# Ciruit_Analyzer.net
KiCad netlist of a schematic drawn in Altium Designer
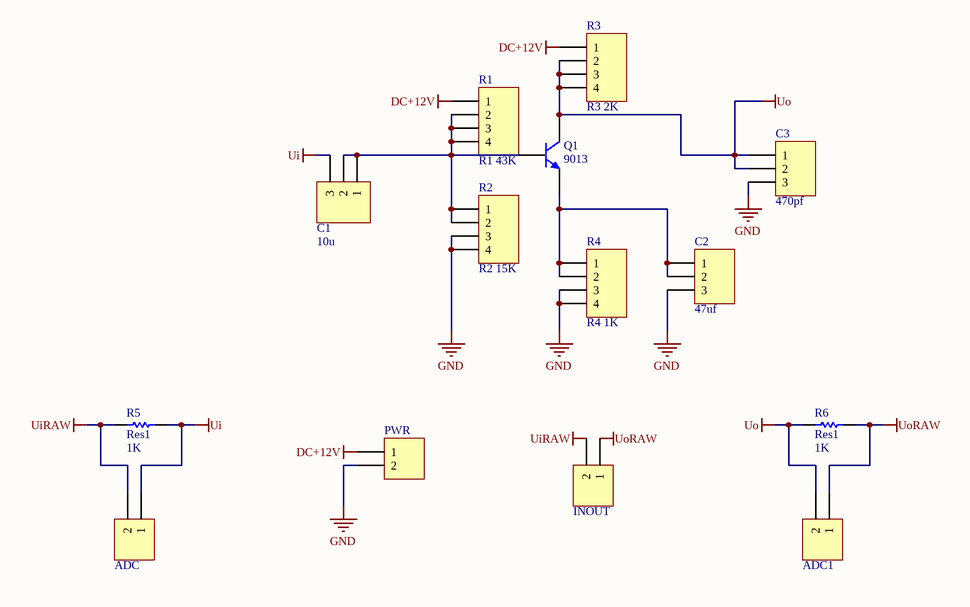
[diagram p0: Ciruit_Analyzer.SchDoc]

(export (version "E")
  (design (tool "Eeschema 10.0.6"))
  (components
    (comp (ref "ADC")
      (value "~")
      (footprint "HDR1X2")
      (description "Header, 2-Pin")
      (fields (field (name "PUBLISHER") "Altium Limited"))
      (libsource (lib "Miscellaneous Connectors") (part "Header 2"))
    )
    (comp (ref "ADC1")
      (value "~")
      (footprint "HDR1X2")
      (description "Header, 2-Pin")
      (fields (field (name "PUBLISHER") "Altium Limited"))
      (libsource (lib "Miscellaneous Connectors") (part "Header 2"))
    )
    (comp (ref "C1")
      (value "10u")
      (footprint "HDR1X3")
      (description "Header, 3-Pin")
      (fields (field (name "PUBLISHER") "Altium Limited"))
      (libsource (lib "") (part "Header 3_1"))
    )
    (comp (ref "C2")
      (value "47uf")
      (footprint "HDR1X3")
      (description "Header, 3-Pin")
      (fields (field (name "PUBLISHER") "Altium Limited"))
      (libsource (lib "Miscellaneous Connectors") (part "Header 3"))
    )
    (comp (ref "C3")
      (value "470pf")
      (footprint "HDR1X3")
      (description "Header, 3-Pin")
      (fields (field (name "PUBLISHER") "Altium Limited"))
      (libsource (lib "Miscellaneous Connectors") (part "Header 3"))
    )
    (comp (ref "INOUT")
      (value "~")
      (footprint "HDR1X2")
      (description "Header, 2-Pin")
      (fields (field (name "PUBLISHER") "Altium Limited"))
      (libsource (lib "Miscellaneous Connectors") (part "Header 2"))
    )
    (comp (ref "PWR")
      (value "~")
      (footprint "HDR1X2")
      (description "Header, 2-Pin")
      (fields (field (name "PUBLISHER") "Altium Limited"))
      (libsource (lib "") (part "Header 2_1"))
    )
    (comp (ref "Q1")
      (value "9013")
      (footprint "TO-92A")
      (description "NPN General Purpose Amplifier")
      (fields (field (name "PUBLISHER") "Altium Limited"))
      (libsource (lib "Miscellaneous Devices") (part "2N3904"))
    )
    (comp (ref "R1")
      (value "R1 43K")
      (footprint "HDR1X4")
      (description "Header, 4-Pin")
      (fields (field (name "PUBLISHER") "Altium Limited"))
      (libsource (lib "Miscellaneous Connectors") (part "Header 4"))
    )
    (comp (ref "R2")
      (value "R2 15K")
      (footprint "HDR1X4")
      (description "Header, 4-Pin")
      (fields (field (name "PUBLISHER") "Altium Limited"))
      (libsource (lib "Miscellaneous Connectors") (part "Header 4"))
    )
    (comp (ref "R3")
      (value "R3 2K")
      (footprint "HDR1X4")
      (description "Header, 4-Pin")
      (fields (field (name "PUBLISHER") "Altium Limited"))
      (libsource (lib "Miscellaneous Connectors") (part "Header 4"))
    )
    (comp (ref "R4")
      (value "R4 1K")
      (footprint "HDR1X4")
      (description "Header, 4-Pin")
      (fields (field (name "PUBLISHER") "Altium Limited"))
      (libsource (lib "Miscellaneous Connectors") (part "Header 4"))
    )
    (comp (ref "R5")
      (value "Res1")
      (footprint "Miscellaneous Devices:6-0805_M")
      (description "Resistor")
      (fields (field (name "ALTIUM_VALUE") "1K") (field (name "PUBLISHER") "Altium Limited"))
      (libsource (lib "Miscellaneous Devices") (part "Res1"))
    )
    (comp (ref "R6")
      (value "Res1")
      (footprint "Miscellaneous Devices:6-0805_M")
      (description "Resistor")
      (fields (field (name "ALTIUM_VALUE") "1K") (field (name "PUBLISHER") "Altium Limited"))
      (libsource (lib "Miscellaneous Devices") (part "Res1"))
    )
  )
  (nets
    (net (code "1") (name "DC+12V") (class "Default")
      (node (ref "PWR") (pin "1") (pinfunction "1_1") (pintype "passive"))
      (node (ref "R1") (pin "1") (pinfunction "1_1") (pintype "passive"))
      (node (ref "R3") (pin "1") (pinfunction "1_1") (pintype "passive"))
    )
    (net (code "2") (name "GND") (class "Default")
      (node (ref "C2") (pin "3") (pinfunction "3_3") (pintype "passive"))
      (node (ref "C3") (pin "3") (pinfunction "3_3") (pintype "passive"))
      (node (ref "PWR") (pin "2") (pinfunction "2_2") (pintype "passive"))
      (node (ref "R2") (pin "3") (pinfunction "3_3") (pintype "passive"))
      (node (ref "R2") (pin "4") (pinfunction "4_4") (pintype "passive"))
      (node (ref "R4") (pin "3") (pinfunction "3_3") (pintype "passive"))
      (node (ref "R4") (pin "4") (pinfunction "4_4") (pintype "passive"))
    )
    (net (code "3") (name "Net-(Q1-B)") (class "Default")
      (node (ref "C1") (pin "1") (pinfunction "1_1") (pintype "passive"))
      (node (ref "C1") (pin "2") (pinfunction "2_2") (pintype "passive"))
      (node (ref "Q1") (pin "2") (pinfunction "B_2") (pintype "passive"))
      (node (ref "R1") (pin "2") (pinfunction "2_2") (pintype "passive"))
      (node (ref "R1") (pin "3") (pinfunction "3_3") (pintype "passive"))
      (node (ref "R1") (pin "4") (pinfunction "4_4") (pintype "passive"))
      (node (ref "R2") (pin "1") (pinfunction "1_1") (pintype "passive"))
      (node (ref "R2") (pin "2") (pinfunction "2_2") (pintype "passive"))
    )
    (net (code "4") (name "Net-(Q1-E)") (class "Default")
      (node (ref "C2") (pin "1") (pinfunction "1_1") (pintype "passive"))
      (node (ref "C2") (pin "2") (pinfunction "2_2") (pintype "passive"))
      (node (ref "Q1") (pin "1") (pinfunction "E_1") (pintype "passive"))
      (node (ref "R4") (pin "1") (pinfunction "1_1") (pintype "passive"))
      (node (ref "R4") (pin "2") (pinfunction "2_2") (pintype "passive"))
    )
    (net (code "5") (name "Ui") (class "Default")
      (node (ref "ADC") (pin "1") (pinfunction "1_1") (pintype "passive"))
      (node (ref "C1") (pin "3") (pinfunction "3_3") (pintype "passive"))
      (node (ref "R5") (pin "2") (pinfunction "2_2") (pintype "passive"))
    )
    (net (code "6") (name "UiRAW") (class "Default")
      (node (ref "ADC") (pin "2") (pinfunction "2_2") (pintype "passive"))
      (node (ref "INOUT") (pin "2") (pinfunction "2_2") (pintype "passive"))
      (node (ref "R5") (pin "1") (pinfunction "1_1") (pintype "passive"))
    )
    (net (code "7") (name "Uo") (class "Default")
      (node (ref "ADC1") (pin "2") (pinfunction "2_2") (pintype "passive"))
      (node (ref "C3") (pin "1") (pinfunction "1_1") (pintype "passive"))
      (node (ref "C3") (pin "2") (pinfunction "2_2") (pintype "passive"))
      (node (ref "Q1") (pin "3") (pinfunction "C_3") (pintype "passive"))
      (node (ref "R3") (pin "2") (pinfunction "2_2") (pintype "passive"))
      (node (ref "R3") (pin "3") (pinfunction "3_3") (pintype "passive"))
      (node (ref "R3") (pin "4") (pinfunction "4_4") (pintype "passive"))
      (node (ref "R6") (pin "1") (pinfunction "1_1") (pintype "passive"))
    )
    (net (code "8") (name "UoRAW") (class "Default")
      (node (ref "ADC1") (pin "1") (pinfunction "1_1") (pintype "passive"))
      (node (ref "INOUT") (pin "1") (pinfunction "1_1") (pintype "passive"))
      (node (ref "R6") (pin "2") (pinfunction "2_2") (pintype "passive"))
    )
  )
)
